# Power.net
KiCad netlist of a schematic drawn in Altium Designer
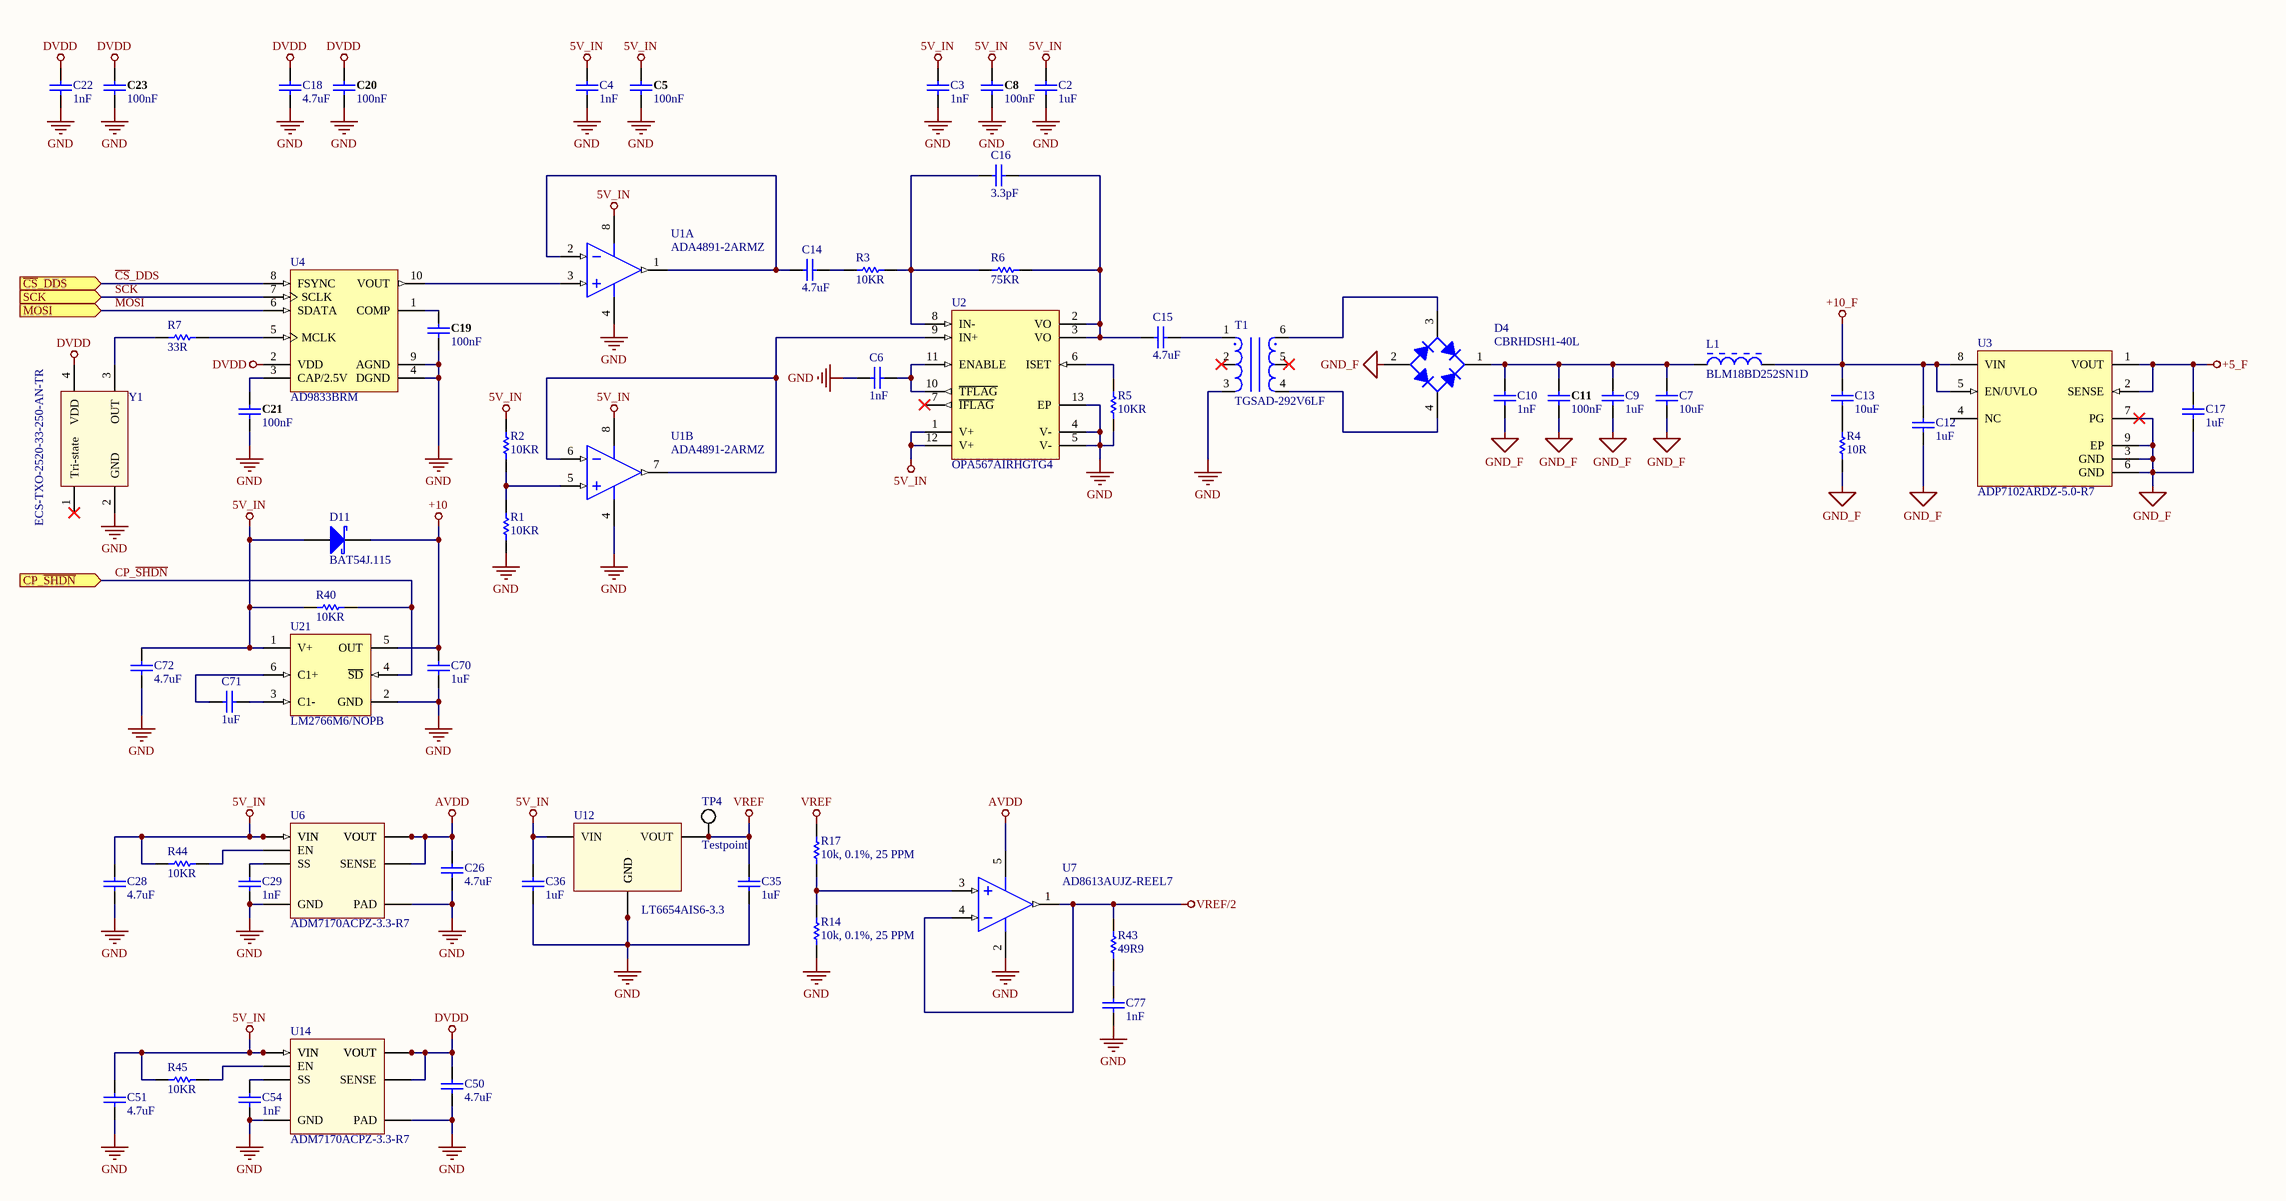
[diagram p0: Power.SchDoc]

(export (version "E")
  (design (tool "Eeschema 10.0.6"))
  (components
    (comp (ref "C2")
      (value "1uF")
      (footprint "CAPC1608X90X40LL15T20")
      (description "CC0603KRX5R7BB105")
      (fields (field (name "TOLERANCE") "±10%") (field (name "MANUFACTURER") "Yageo"))
      (libsource (lib "Altium Content Vault") (part "CAP-NP-2"))
    )
    (comp (ref "C3")
      (value "1nF")
      (footprint "CAPC1005X55X25ML5T10")
      (description "CC0402JRX7R9BB102")
      (fields (field (name "MANUFACTURER") "Yageo") (field (name "TOLERANCE") "10%"))
      (libsource (lib "Altium Content Vault") (part "CAP-NP-2"))
    )
    (comp (ref "C4")
      (value "1nF")
      (footprint "CAPC1005X55X25ML5T10")
      (description "CC0402JRX7R9BB102")
      (fields (field (name "MANUFACTURER") "Yageo") (field (name "TOLERANCE") "10%"))
      (libsource (lib "Altium Content Vault") (part "CAP-NP-2"))
    )
    (comp (ref "C5")
      (value "100nF")
      (footprint "CAPC1005")
      (description "CC0402KRX7R7BB104")
      (fields (field (name "TOLERANCE") "10 %") (field (name "PUBLISHER") "Altium"))
      (libsource (lib "Altium Content Vault") (part "CAP-NP"))
    )
    (comp (ref "C6")
      (value "1nF")
      (footprint "CAPC1005X55X25ML5T10")
      (description "CC0402JRX7R9BB102")
      (fields (field (name "MANUFACTURER") "Yageo") (field (name "TOLERANCE") "10%"))
      (libsource (lib "Altium Content Vault") (part "CAP-NP-2"))
    )
    (comp (ref "C7")
      (value "10uF")
      (footprint "CAPC2013X95X45ML10T25")
      (description "GRM219R61E106KA12D")
      (fields (field (name "MANUFACTURER") "Murata"))
      (libsource (lib "Altium Content Vault") (part "CAP"))
    )
    (comp (ref "C8")
      (value "100nF")
      (footprint "CAPC1005")
      (description "CC0402KRX7R7BB104")
      (fields (field (name "TOLERANCE") "10 %") (field (name "PUBLISHER") "Altium"))
      (libsource (lib "Altium Content Vault") (part "CAP-NP"))
    )
    (comp (ref "C9")
      (value "1uF")
      (footprint "CAPC1608X90X40LL15T20")
      (description "CC0603KRX5R7BB105")
      (fields (field (name "TOLERANCE") "±10%") (field (name "MANUFACTURER") "Yageo"))
      (libsource (lib "Altium Content Vault") (part "CAP-NP-2"))
    )
    (comp (ref "C10")
      (value "1nF")
      (footprint "CAPC1005X55X25ML5T10")
      (description "CC0402JRX7R9BB102")
      (fields (field (name "MANUFACTURER") "Yageo") (field (name "TOLERANCE") "10%"))
      (libsource (lib "Altium Content Vault") (part "CAP-NP-2"))
    )
    (comp (ref "C11")
      (value "100nF")
      (footprint "CAPC1005")
      (description "CC0402KRX7R7BB104")
      (fields (field (name "TOLERANCE") "10 %") (field (name "PUBLISHER") "Altium"))
      (libsource (lib "Altium Content Vault") (part "CAP-NP"))
    )
    (comp (ref "C12")
      (value "1uF")
      (footprint "CAPC1608X90X40LL15T20")
      (description "CC0603KRX5R7BB105")
      (fields (field (name "TOLERANCE") "±10%") (field (name "MANUFACTURER") "Yageo"))
      (libsource (lib "Altium Content Vault") (part "CAP-NP-2"))
    )
    (comp (ref "C13")
      (value "10uF")
      (footprint "CAPC2013X95X45ML10T25")
      (description "GRM219R61E106KA12D")
      (fields (field (name "MANUFACTURER") "Murata"))
      (libsource (lib "Altium Content Vault") (part "CAP"))
    )
    (comp (ref "C14")
      (value "4.7uF")
      (footprint "CAPC1608X90X40LL15T20")
      (description "CC0603KRX5R6BB475")
      (fields (field (name "TOLERANCE") "±10%") (field (name "MANUFACTURER") "Yageo"))
      (libsource (lib "Altium Content Vault") (part "CAP-NP-2"))
    )
    (comp (ref "C15")
      (value "4.7uF")
      (footprint "CAPC1608X90X40LL15T20")
      (description "CC0603KRX5R6BB475")
      (fields (field (name "TOLERANCE") "±10%") (field (name "MANUFACTURER") "Yageo"))
      (libsource (lib "Altium Content Vault") (part "CAP-NP-2"))
    )
    (comp (ref "C16")
      (value "3.3pF")
      (footprint "CAPC1005X55X25ML05T05")
      (description "CC0402CRNPO9BN3R3")
      (fields (field (name "TOLERANCE") "5%") (field (name "MANUFACTURER") "Yageo"))
      (libsource (lib "Altium Content Vault") (part "CAP-NP-2"))
    )
    (comp (ref "C17")
      (value "1uF")
      (footprint "CAPC1608X90X40LL15T20")
      (description "CC0603KRX5R7BB105")
      (fields (field (name "TOLERANCE") "±10%") (field (name "MANUFACTURER") "Yageo"))
      (libsource (lib "Altium Content Vault") (part "CAP-NP-2"))
    )
    (comp (ref "C18")
      (value "4.7uF")
      (footprint "CAPC1608X90X40LL15T20")
      (description "CC0603KRX5R6BB475")
      (fields (field (name "TOLERANCE") "±10%") (field (name "MANUFACTURER") "Yageo"))
      (libsource (lib "Altium Content Vault") (part "CAP-NP-2"))
    )
    (comp (ref "C19")
      (value "100nF")
      (footprint "CAPC1005")
      (description "CC0402KRX7R7BB104")
      (fields (field (name "TOLERANCE") "10 %") (field (name "PUBLISHER") "Altium"))
      (libsource (lib "Altium Content Vault") (part "CAP-NP"))
    )
    (comp (ref "C20")
      (value "100nF")
      (footprint "CAPC1005")
      (description "CC0402KRX7R7BB104")
      (fields (field (name "TOLERANCE") "10 %") (field (name "PUBLISHER") "Altium"))
      (libsource (lib "Altium Content Vault") (part "CAP-NP"))
    )
    (comp (ref "C21")
      (value "100nF")
      (footprint "CAPC1005")
      (description "CC0402KRX7R7BB104")
      (fields (field (name "TOLERANCE") "10 %") (field (name "PUBLISHER") "Altium"))
      (libsource (lib "Altium Content Vault") (part "CAP-NP"))
    )
    (comp (ref "C22")
      (value "1nF")
      (footprint "CAPC1005X55X25ML5T10")
      (description "CC0402JRX7R9BB102")
      (fields (field (name "MANUFACTURER") "Yageo") (field (name "TOLERANCE") "10%"))
      (libsource (lib "Altium Content Vault") (part "CAP-NP-2"))
    )
    (comp (ref "C23")
      (value "100nF")
      (footprint "CAPC1005")
      (description "CC0402KRX7R7BB104")
      (fields (field (name "TOLERANCE") "10 %") (field (name "PUBLISHER") "Altium"))
      (libsource (lib "Altium Content Vault") (part "CAP-NP"))
    )
    (comp (ref "C26")
      (value "4.7uF")
      (footprint "CAPC1608X90X40LL15T20")
      (description "CC0603KRX5R6BB475")
      (fields (field (name "TOLERANCE") "±10%") (field (name "MANUFACTURER") "Yageo"))
      (libsource (lib "Altium Content Vault") (part "CAP-NP-2"))
    )
    (comp (ref "C28")
      (value "4.7uF")
      (footprint "CAPC1608X90X40LL15T20")
      (description "CC0603KRX5R6BB475")
      (fields (field (name "TOLERANCE") "±10%") (field (name "MANUFACTURER") "Yageo"))
      (libsource (lib "Altium Content Vault") (part "CAP-NP-2"))
    )
    (comp (ref "C29")
      (value "1nF")
      (footprint "CAPC1005X55X25ML5T10")
      (description "CC0402JRX7R9BB102")
      (fields (field (name "MANUFACTURER") "Yageo") (field (name "TOLERANCE") "10%"))
      (libsource (lib "Altium Content Vault") (part "CAP-NP-2"))
    )
    (comp (ref "C35")
      (value "1uF")
      (footprint "CAPC1608X90X40LL15T20")
      (description "CC0603KRX5R7BB105")
      (fields (field (name "TOLERANCE") "±10%") (field (name "MANUFACTURER") "Yageo"))
      (libsource (lib "Altium Content Vault") (part "CAP-NP-2"))
    )
    (comp (ref "C36")
      (value "1uF")
      (footprint "CAPC1608X90X40LL15T20")
      (description "CC0603KRX5R7BB105")
      (fields (field (name "TOLERANCE") "±10%") (field (name "MANUFACTURER") "Yageo"))
      (libsource (lib "Altium Content Vault") (part "CAP-NP-2"))
    )
    (comp (ref "C50")
      (value "4.7uF")
      (footprint "CAPC1608X90X40LL15T20")
      (description "CC0603KRX5R6BB475")
      (fields (field (name "TOLERANCE") "±10%") (field (name "MANUFACTURER") "Yageo"))
      (libsource (lib "Altium Content Vault") (part "CAP-NP-2"))
    )
    (comp (ref "C51")
      (value "4.7uF")
      (footprint "CAPC1608X90X40LL15T20")
      (description "CC0603KRX5R6BB475")
      (fields (field (name "TOLERANCE") "±10%") (field (name "MANUFACTURER") "Yageo"))
      (libsource (lib "Altium Content Vault") (part "CAP-NP-2"))
    )
    (comp (ref "C54")
      (value "1nF")
      (footprint "CAPC1005X55X25ML5T10")
      (description "CC0402JRX7R9BB102")
      (fields (field (name "MANUFACTURER") "Yageo") (field (name "TOLERANCE") "10%"))
      (libsource (lib "Altium Content Vault") (part "CAP-NP-2"))
    )
    (comp (ref "C70")
      (value "1uF")
      (footprint "CAPC1608X90X40LL15T20")
      (description "CC0603KRX5R7BB105")
      (fields (field (name "TOLERANCE") "±10%") (field (name "MANUFACTURER") "Yageo"))
      (libsource (lib "Altium Content Vault") (part "CAP-NP-2"))
    )
    (comp (ref "C71")
      (value "1uF")
      (footprint "CAPC1608X90X40LL15T20")
      (description "CC0603KRX5R7BB105")
      (fields (field (name "TOLERANCE") "±10%") (field (name "MANUFACTURER") "Yageo"))
      (libsource (lib "Altium Content Vault") (part "CAP-NP-2"))
    )
    (comp (ref "C72")
      (value "4.7uF")
      (footprint "CAPC1608X90X40LL15T20")
      (description "CC0603KRX5R6BB475")
      (fields (field (name "TOLERANCE") "±10%") (field (name "MANUFACTURER") "Yageo"))
      (libsource (lib "Altium Content Vault") (part "CAP-NP-2"))
    )
    (comp (ref "C77")
      (value "1nF")
      (footprint "CAPC1005X55X25ML5T10")
      (description "CC0402JRX7R9BB102")
      (fields (field (name "MANUFACTURER") "Yageo") (field (name "TOLERANCE") "10%"))
      (libsource (lib "Altium Content Vault") (part "CAP-NP-2"))
    )
    (comp (ref "D4")
      (value "CBRHDSH1-40L")
      (footprint "HDDIP")
      (libsource (lib "LocalLib") (part "CBRHDSH1-40L"))
    )
    (comp (ref "D11")
      (value "BAT54J.115")
      (footprint "SOD-323")
      (libsource (lib "LocalLib") (part "BAT54J.115"))
    )
    (comp (ref "L1")
      (value "BLM18BD252SN1D")
      (footprint "MURA-BLM18-F-H1-CHIP-2_V")
      (fields (field (name "MANUFACTURER") "Murata"))
      (libsource (lib "Altium Content Vault") (part "MURA-FB-2"))
    )
    (comp (ref "R1")
      (value "10KR")
      (footprint "RESC1005X40X25LL05T10")
      (description "RC0402FR-0710KL")
      (fields (field (name "MANUFACTURER") "Yageo / Phycomp"))
      (libsource (lib "Altium Content Vault") (part "RES"))
    )
    (comp (ref "R2")
      (value "10KR")
      (footprint "RESC1005X40X25LL05T10")
      (description "RC0402FR-0710KL")
      (fields (field (name "MANUFACTURER") "Yageo / Phycomp"))
      (libsource (lib "Altium Content Vault") (part "RES"))
    )
    (comp (ref "R3")
      (value "10KR")
      (footprint "RESC1005X40X25LL05T10")
      (description "RC0402FR-0710KL")
      (fields (field (name "MANUFACTURER") "Yageo / Phycomp"))
      (libsource (lib "Altium Content Vault") (part "RES"))
    )
    (comp (ref "R4")
      (value "10R")
      (footprint "RESC1608X55X25LL10T15")
      (description "RC0603FR-0710RL")
      (fields (field (name "MANUFACTURER") "Yageo"))
      (libsource (lib "Altium Content Vault") (part "RES-2"))
    )
    (comp (ref "R5")
      (value "10KR")
      (footprint "RESC1005X40X25LL05T10")
      (description "RC0402FR-0710KL")
      (fields (field (name "MANUFACTURER") "Yageo / Phycomp"))
      (libsource (lib "Altium Content Vault") (part "RES"))
    )
    (comp (ref "R6")
      (value "75KR")
      (footprint "RESC1005X40X25LL05T10")
      (description "RC0402FR-0775KL")
      (fields (field (name "MANUFACTURER") "Yageo / Phycomp"))
      (libsource (lib "Altium Content Vault") (part "RES"))
    )
    (comp (ref "R7")
      (value "33R")
      (footprint "RESC1005X40X25LL05T10")
      (description "RC0402FR-0733RL")
      (fields (field (name "MANUFACTURER") "Yageo / Phycomp"))
      (libsource (lib "Altium Content Vault") (part "RES"))
    )
    (comp (ref "R14")
      (value "10k, 0.1%, 25 PPM")
      (footprint "RT0603")
      (description "RT0603BRD0710KL")
      (libsource (lib "LocalLib") (part "RT0603BRD0710KL"))
    )
    (comp (ref "R17")
      (value "10k, 0.1%, 25 PPM")
      (footprint "RT0603")
      (description "RT0603BRD0710KL")
      (libsource (lib "LocalLib") (part "RT0603BRD0710KL"))
    )
    (comp (ref "R40")
      (value "10KR")
      (footprint "RESC1005X40X25LL05T10")
      (description "RC0402FR-0710KL")
      (fields (field (name "MANUFACTURER") "Yageo / Phycomp"))
      (libsource (lib "Altium Content Vault") (part "RES"))
    )
    (comp (ref "R43")
      (value "49R9")
      (footprint "RESC1005X40X25LL05T10")
      (description "RC0402FR-0749R9L")
      (fields (field (name "MANUFACTURER") "Yageo / Phycomp"))
      (libsource (lib "Altium Content Vault") (part "RES"))
    )
    (comp (ref "R44")
      (value "10KR")
      (footprint "RESC1005X40X25LL05T10")
      (description "RC0402FR-0710KL")
      (fields (field (name "MANUFACTURER") "Yageo / Phycomp"))
      (libsource (lib "Altium Content Vault") (part "RES"))
    )
    (comp (ref "R45")
      (value "10KR")
      (footprint "RESC1005X40X25LL05T10")
      (description "RC0402FR-0710KL")
      (fields (field (name "MANUFACTURER") "Yageo / Phycomp"))
      (libsource (lib "Altium Content Vault") (part "RES"))
    )
    (comp (ref "T1")
      (value "TGSAD-292V6LF")
      (footprint "TGSAD-V6LF")
      (description "1:5")
      (libsource (lib "LocalLib") (part "TGSAD-292V6LF"))
    )
    (comp (ref "TP4")
      (value "Testpoint")
      (footprint "TESTPOINT")
      (libsource (lib "LocalLib") (part "Testpoint"))
    )
    (comp (ref "U1")
      (value "ADA4891-2ARMZ")
      (footprint "ADI-RM-8_L")
      (fields (field (name "GENERIC PART NUMBER") "ADA4891-2") (field (name "MANUFACTURER") "Analog Devices"))
      (libsource (lib "Altium Content Vault") (part "ADI-AD8XXX_823_A48X1-X-8"))
    )
    (comp (ref "U2")
      (value "OPA567AIRHGTG4")
      (footprint "TI-RHG12-3120X3120TP_V")
      (libsource (lib "Altium Content Vault") (part "TI-OPA567-RHG12"))
    )
    (comp (ref "U3")
      (value "ADP7102ARDZ-5.0-R7")
      (footprint "ADI-RD-8-2_N")
      (description "300 mA, Low Noise, CMOS LDO, 3.3 to 20 V Vin, 5 V Vout, Industrial, 8-pin SOIC (RD-8-2), Reel")
      (fields (field (name "MANUFACTURER") "Analog Devices"))
      (libsource (lib "Altium Content Vault") (part "ADI-ADP7102-RD-8-2"))
    )
    (comp (ref "U4")
      (value "AD9833BRM")
      (footprint "ADI-RM-10_N")
      (libsource (lib "Altium Content Vault") (part "ADI-AD9833-RM-10"))
    )
    (comp (ref "U6")
      (value "ADM7170ACPZ-3.3-R7")
      (footprint "LFCSP8")
      (libsource (lib "LocalLib") (part "ADM7170ACPZ-3.3-R7"))
    )
    (comp (ref "U7")
      (value "AD8613AUJZ-REEL7")
      (footprint "TSOT-23-5")
      (description "Low Cost Micropower, Low Noise CMOS\r\nRail-to-Rail, Input/Output Operational Amplifiers")
      (libsource (lib "LocalLib") (part "AD8613AUJZ-REEL7"))
    )
    (comp (ref "U12")
      (value "LT6654AIS6-3.3")
      (footprint "SOT-23-6")
      (description "Precision Wide Supply High Output Drive Low Noise Reference")
      (libsource (lib "LocalLib") (part "LT6654AIS6-3.3"))
    )
    (comp (ref "U14")
      (value "ADM7170ACPZ-3.3-R7")
      (footprint "LFCSP8")
      (libsource (lib "LocalLib") (part "ADM7170ACPZ-3.3-R7"))
    )
    (comp (ref "U21")
      (value "LM2766M6/NOPB")
      (footprint "DBV0006A_N")
      (description "Switched Capacitor Voltage Converter, 6-pin SOT-23, Pb-Free")
      (fields (field (name "MANUFACTURER") "Texas Instruments"))
      (libsource (lib "Altium Content Vault") (part "PM-CHP-LM2766M6-6"))
    )
    (comp (ref "Y1")
      (value "ECS-TXO-2520-33-250-AN-TR")
      (footprint "XTAL_ECS-TXO-2520-33-250")
      (libsource (lib "LocalLib") (part "ECS-TXO-2520-33-250-AN-TR"))
    )
  )
  (nets
    (net (code "1") (name "+5_F") (class "Default")
      (node (ref "C17") (pin "1") (pinfunction "1_1") (pintype "passive"))
      (node (ref "U3") (pin "1") (pinfunction "VOUT_1") (pintype "power_in"))
      (node (ref "U3") (pin "2") (pinfunction "SENSE_2") (pintype "input"))
    )
    (net (code "2") (name "+10") (class "Default")
      (node (ref "C70") (pin "2") (pinfunction "2_2") (pintype "passive"))
      (node (ref "D11") (pin "1") (pinfunction "K_1") (pintype "passive"))
      (node (ref "U21") (pin "5") (pinfunction "OUT_5") (pintype "power_in"))
    )
    (net (code "3") (name "+10_F") (class "Default")
      (node (ref "C12") (pin "1") (pinfunction "1_1") (pintype "passive"))
      (node (ref "C13") (pin "2") (pinfunction "2_2") (pintype "passive"))
      (node (ref "L1") (pin "2") (pinfunction "2_2") (pintype "passive"))
      (node (ref "U3") (pin "5") (pinfunction "EN/UVLO_5") (pintype "input"))
      (node (ref "U3") (pin "8") (pinfunction "VIN_8") (pintype "power_in"))
    )
    (net (code "4") (name "/CP_~{SHDN}") (class "Default")
      (node (ref "R40") (pin "1") (pinfunction "1_1") (pintype "passive"))
      (node (ref "U21") (pin "4") (pinfunction "~{SD}_4") (pintype "input"))
    )
    (net (code "5") (name "/MOSI") (class "Default")
      (node (ref "U4") (pin "6") (pinfunction "SDATA_6") (pintype "input"))
    )
    (net (code "6") (name "/SCK") (class "Default")
      (node (ref "U4") (pin "7") (pinfunction "SCLK_7") (pintype "input"))
    )
    (net (code "7") (name "/~{CS}_DDS") (class "Default")
      (node (ref "U4") (pin "8") (pinfunction "FSYNC_8") (pintype "input"))
    )
    (net (code "8") (name "5V_IN") (class "Default")
      (node (ref "C2") (pin "1") (pinfunction "1_1") (pintype "passive"))
      (node (ref "C28") (pin "2") (pinfunction "2_2") (pintype "passive"))
      (node (ref "C3") (pin "2") (pinfunction "2_2") (pintype "passive"))
      (node (ref "C36") (pin "1") (pinfunction "1_1") (pintype "passive"))
      (node (ref "C4") (pin "2") (pinfunction "2_2") (pintype "passive"))
      (node (ref "C5") (pin "1") (pinfunction "1_1") (pintype "passive"))
      (node (ref "C51") (pin "2") (pinfunction "2_2") (pintype "passive"))
      (node (ref "C72") (pin "2") (pinfunction "2_2") (pintype "passive"))
      (node (ref "C8") (pin "1") (pinfunction "1_1") (pintype "passive"))
      (node (ref "D11") (pin "2") (pinfunction "A_2") (pintype "passive"))
      (node (ref "R2") (pin "1") (pinfunction "1_1") (pintype "passive"))
      (node (ref "R40") (pin "2") (pinfunction "2_2") (pintype "passive"))
      (node (ref "R44") (pin "2") (pinfunction "2_2") (pintype "passive"))
      (node (ref "R45") (pin "2") (pinfunction "2_2") (pintype "passive"))
      (node (ref "U1") (pin "8") (pinfunction "+VS_8") (pintype "power_in"))
      (node (ref "U12") (pin "4") (pinfunction "VIN_4") (pintype "passive"))
      (node (ref "U14") (pin "7") (pinfunction "VIN_7") (pintype "input"))
      (node (ref "U14") (pin "8") (pinfunction "VIN_8") (pintype "input"))
      (node (ref "U2") (pin "1") (pinfunction "V+_1") (pintype "power_in"))
      (node (ref "U2") (pin "12") (pinfunction "V+_12") (pintype "power_in"))
      (node (ref "U21") (pin "1") (pinfunction "V+_1") (pintype "power_in"))
      (node (ref "U6") (pin "7") (pinfunction "VIN_7") (pintype "input"))
      (node (ref "U6") (pin "8") (pinfunction "VIN_8") (pintype "input"))
    )
    (net (code "9") (name "AVDD") (class "Default")
      (node (ref "C26") (pin "2") (pinfunction "2_2") (pintype "passive"))
      (node (ref "U6") (pin "1") (pinfunction "VOUT_1") (pintype "passive"))
      (node (ref "U6") (pin "2") (pinfunction "VOUT_2") (pintype "passive"))
      (node (ref "U6") (pin "3") (pinfunction "SENSE_3") (pintype "passive"))
      (node (ref "U7") (pin "5") (pinfunction "5_5") (pintype "passive"))
    )
    (net (code "10") (name "DVDD") (class "Default")
      (node (ref "C18") (pin "2") (pinfunction "2_2") (pintype "passive"))
      (node (ref "C20") (pin "1") (pinfunction "1_1") (pintype "passive"))
      (node (ref "C22") (pin "2") (pinfunction "2_2") (pintype "passive"))
      (node (ref "C23") (pin "1") (pinfunction "1_1") (pintype "passive"))
      (node (ref "C50") (pin "2") (pinfunction "2_2") (pintype "passive"))
      (node (ref "U14") (pin "1") (pinfunction "VOUT_1") (pintype "passive"))
      (node (ref "U14") (pin "2") (pinfunction "VOUT_2") (pintype "passive"))
      (node (ref "U14") (pin "3") (pinfunction "SENSE_3") (pintype "passive"))
      (node (ref "U4") (pin "2") (pinfunction "VDD_2") (pintype "power_in"))
      (node (ref "Y1") (pin "4") (pinfunction "VDD_4") (pintype "passive"))
    )
    (net (code "11") (name "GND") (class "Default")
      (node (ref "C18") (pin "1") (pinfunction "1_1") (pintype "passive"))
      (node (ref "C19") (pin "2") (pinfunction "2_2") (pintype "passive"))
      (node (ref "C2") (pin "2") (pinfunction "2_2") (pintype "passive"))
      (node (ref "C20") (pin "2") (pinfunction "2_2") (pintype "passive"))
      (node (ref "C21") (pin "2") (pinfunction "2_2") (pintype "passive"))
      (node (ref "C22") (pin "1") (pinfunction "1_1") (pintype "passive"))
      (node (ref "C23") (pin "2") (pinfunction "2_2") (pintype "passive"))
      (node (ref "C26") (pin "1") (pinfunction "1_1") (pintype "passive"))
      (node (ref "C28") (pin "1") (pinfunction "1_1") (pintype "passive"))
      (node (ref "C29") (pin "1") (pinfunction "1_1") (pintype "passive"))
      (node (ref "C3") (pin "1") (pinfunction "1_1") (pintype "passive"))
      (node (ref "C35") (pin "2") (pinfunction "2_2") (pintype "passive"))
      (node (ref "C36") (pin "2") (pinfunction "2_2") (pintype "passive"))
      (node (ref "C4") (pin "1") (pinfunction "1_1") (pintype "passive"))
      (node (ref "C5") (pin "2") (pinfunction "2_2") (pintype "passive"))
      (node (ref "C50") (pin "1") (pinfunction "1_1") (pintype "passive"))
      (node (ref "C51") (pin "1") (pinfunction "1_1") (pintype "passive"))
      (node (ref "C54") (pin "1") (pinfunction "1_1") (pintype "passive"))
      (node (ref "C6") (pin "2") (pinfunction "2_2") (pintype "passive"))
      (node (ref "C70") (pin "1") (pinfunction "1_1") (pintype "passive"))
      (node (ref "C72") (pin "1") (pinfunction "1_1") (pintype "passive"))
      (node (ref "C77") (pin "2") (pinfunction "2_2") (pintype "passive"))
      (node (ref "C8") (pin "2") (pinfunction "2_2") (pintype "passive"))
      (node (ref "R1") (pin "2") (pinfunction "2_2") (pintype "passive"))
      (node (ref "R14") (pin "1") (pinfunction "1_1") (pintype "passive"))
      (node (ref "R5") (pin "1") (pinfunction "1_1") (pintype "passive"))
      (node (ref "T1") (pin "3") (pinfunction "3_3") (pintype "passive"))
      (node (ref "U1") (pin "4") (pinfunction "-VS_4") (pintype "power_in"))
      (node (ref "U12") (pin "1") (pinfunction "GND_1") (pintype "passive"))
      (node (ref "U12") (pin "2") (pinfunction "GND_2") (pintype "passive"))
      (node (ref "U14") (pin "6") (pinfunction "GND_6") (pintype "passive"))
      (node (ref "U14") (pin "9") (pinfunction "PAD_9") (pintype "passive"))
      (node (ref "U2") (pin "13") (pinfunction "EP_13") (pintype "passive"))
      (node (ref "U2") (pin "4") (pinfunction "V-_4") (pintype "power_in"))
      (node (ref "U2") (pin "5") (pinfunction "V-_5") (pintype "power_in"))
      (node (ref "U21") (pin "2") (pinfunction "GND_2") (pintype "power_in"))
      (node (ref "U4") (pin "4") (pinfunction "DGND_4") (pintype "power_in"))
      (node (ref "U4") (pin "9") (pinfunction "AGND_9") (pintype "power_in"))
      (node (ref "U6") (pin "6") (pinfunction "GND_6") (pintype "passive"))
      (node (ref "U6") (pin "9") (pinfunction "PAD_9") (pintype "passive"))
      (node (ref "U7") (pin "2") (pinfunction "2_2") (pintype "passive"))
      (node (ref "Y1") (pin "2") (pinfunction "GND_2") (pintype "passive"))
    )
    (net (code "12") (name "GND_F") (class "Default")
      (node (ref "C10") (pin "1") (pinfunction "1_1") (pintype "passive"))
      (node (ref "C11") (pin "2") (pinfunction "2_2") (pintype "passive"))
      (node (ref "C12") (pin "2") (pinfunction "2_2") (pintype "passive"))
      (node (ref "C17") (pin "2") (pinfunction "2_2") (pintype "passive"))
      (node (ref "C7") (pin "1") (pinfunction "1_1") (pintype "passive"))
      (node (ref "C9") (pin "2") (pinfunction "2_2") (pintype "passive"))
      (node (ref "D4") (pin "2") (pinfunction "A_2") (pintype "passive"))
      (node (ref "R4") (pin "1") (pinfunction "1_1") (pintype "passive"))
      (node (ref "U3") (pin "3") (pinfunction "GND_3") (pintype "power_in"))
      (node (ref "U3") (pin "6") (pinfunction "GND_6") (pintype "power_in"))
      (node (ref "U3") (pin "7") (pinfunction "PG_7") (pintype "open_collector"))
      (node (ref "U3") (pin "9") (pinfunction "EP_9") (pintype "power_in"))
    )
    (net (code "13") (name "Net-(C13-Pad1)") (class "Default")
      (node (ref "C13") (pin "1") (pinfunction "1_1") (pintype "passive"))
      (node (ref "R4") (pin "2") (pinfunction "2_2") (pintype "passive"))
    )
    (net (code "14") (name "Net-(C14-Pad1)") (class "Default")
      (node (ref "C14") (pin "1") (pinfunction "1_1") (pintype "passive"))
      (node (ref "R3") (pin "1") (pinfunction "1_1") (pintype "passive"))
    )
    (net (code "15") (name "Net-(C15-Pad1)") (class "Default")
      (node (ref "C15") (pin "1") (pinfunction "1_1") (pintype "passive"))
      (node (ref "T1") (pin "1") (pinfunction "1_1") (pintype "passive"))
    )
    (net (code "16") (name "Net-(C15-Pad2)") (class "Default")
      (node (ref "C15") (pin "2") (pinfunction "2_2") (pintype "passive"))
      (node (ref "C16") (pin "2") (pinfunction "2_2") (pintype "passive"))
      (node (ref "R6") (pin "2") (pinfunction "2_2") (pintype "passive"))
      (node (ref "U2") (pin "2") (pinfunction "VO_2") (pintype "tri_state"))
      (node (ref "U2") (pin "3") (pinfunction "VO_3") (pintype "tri_state"))
    )
    (net (code "17") (name "Net-(C77-Pad1)") (class "Default")
      (node (ref "C77") (pin "1") (pinfunction "1_1") (pintype "passive"))
      (node (ref "R43") (pin "2") (pinfunction "2_2") (pintype "passive"))
    )
    (net (code "18") (name "Net-(D4-C-Pad3)") (class "Default")
      (node (ref "D4") (pin "3") (pinfunction "C_3") (pintype "passive"))
      (node (ref "T1") (pin "6") (pinfunction "6_6") (pintype "passive"))
    )
    (net (code "19") (name "Net-(D4-C-Pad4)") (class "Default")
      (node (ref "D4") (pin "4") (pinfunction "C_4") (pintype "passive"))
      (node (ref "T1") (pin "4") (pinfunction "4_4") (pintype "passive"))
    )
    (net (code "20") (name "Net-(D4-K)") (class "Default")
      (node (ref "C10") (pin "2") (pinfunction "2_2") (pintype "passive"))
      (node (ref "C11") (pin "1") (pinfunction "1_1") (pintype "passive"))
      (node (ref "C7") (pin "2") (pinfunction "2_2") (pintype "passive"))
      (node (ref "C9") (pin "1") (pinfunction "1_1") (pintype "passive"))
      (node (ref "D4") (pin "1") (pinfunction "K_1") (pintype "passive"))
      (node (ref "L1") (pin "1") (pinfunction "1_1") (pintype "passive"))
    )
    (net (code "21") (name "Net-(R14-Pad2)") (class "Default")
      (node (ref "R14") (pin "2") (pinfunction "2_2") (pintype "passive"))
      (node (ref "R17") (pin "1") (pinfunction "1_1") (pintype "passive"))
      (node (ref "U7") (pin "3") (pinfunction "3_3") (pintype "input"))
    )
    (net (code "22") (name "Net-(U1A-+IN_1)") (class "Default")
      (node (ref "U1") (pin "3") (pinfunction "+IN_1_3") (pintype "input"))
      (node (ref "U4") (pin "10") (pinfunction "VOUT_10") (pintype "output"))
    )
    (net (code "23") (name "Net-(U1A--IN_1)") (class "Default")
      (node (ref "C14") (pin "2") (pinfunction "2_2") (pintype "passive"))
      (node (ref "U1") (pin "1") (pinfunction "OUT_1_1") (pintype "output"))
      (node (ref "U1") (pin "2") (pinfunction "-IN_1_2") (pintype "input"))
    )
    (net (code "24") (name "Net-(U1B-+IN_2)") (class "Default")
      (node (ref "R1") (pin "1") (pinfunction "1_1") (pintype "passive"))
      (node (ref "R2") (pin "2") (pinfunction "2_2") (pintype "passive"))
      (node (ref "U1") (pin "5") (pinfunction "+IN_2_5") (pintype "input"))
    )
    (net (code "25") (name "Net-(U1B--IN_2)") (class "Default")
      (node (ref "U1") (pin "6") (pinfunction "-IN_2_6") (pintype "input"))
      (node (ref "U1") (pin "7") (pinfunction "OUT_2_7") (pintype "output"))
      (node (ref "U2") (pin "9") (pinfunction "IN+_9") (pintype "input"))
    )
    (net (code "26") (name "Net-(U2-ENABLE)") (class "Default")
      (node (ref "C6") (pin "1") (pinfunction "1_1") (pintype "passive"))
      (node (ref "U2") (pin "10") (pinfunction "~{TFLAG}_10") (pintype "output"))
      (node (ref "U2") (pin "11") (pinfunction "ENABLE_11") (pintype "input"))
    )
    (net (code "27") (name "Net-(U2-IN-)") (class "Default")
      (node (ref "C16") (pin "1") (pinfunction "1_1") (pintype "passive"))
      (node (ref "R3") (pin "2") (pinfunction "2_2") (pintype "passive"))
      (node (ref "R6") (pin "1") (pinfunction "1_1") (pintype "passive"))
      (node (ref "U2") (pin "8") (pinfunction "IN-_8") (pintype "input"))
    )
    (net (code "28") (name "Net-(U2-ISET)") (class "Default")
      (node (ref "R5") (pin "2") (pinfunction "2_2") (pintype "passive"))
      (node (ref "U2") (pin "6") (pinfunction "ISET_6") (pintype "input"))
    )
    (net (code "29") (name "Net-(U4-CAP{slash}2.5V)") (class "Default")
      (node (ref "C21") (pin "1") (pinfunction "1_1") (pintype "passive"))
      (node (ref "U4") (pin "3") (pinfunction "CAP/2.5V_3") (pintype "power_in"))
    )
    (net (code "30") (name "Net-(U4-COMP)") (class "Default")
      (node (ref "C19") (pin "1") (pinfunction "1_1") (pintype "passive"))
      (node (ref "U4") (pin "1") (pinfunction "COMP_1") (pintype "passive"))
    )
    (net (code "31") (name "Net-(U4-MCLK)") (class "Default")
      (node (ref "R7") (pin "2") (pinfunction "2_2") (pintype "passive"))
      (node (ref "U4") (pin "5") (pinfunction "MCLK_5") (pintype "input"))
    )
    (net (code "32") (name "Net-(U6-EN)") (class "Default")
      (node (ref "R44") (pin "1") (pinfunction "1_1") (pintype "passive"))
      (node (ref "U6") (pin "5") (pinfunction "EN_5") (pintype "passive"))
    )
    (net (code "33") (name "Net-(U6-SS)") (class "Default")
      (node (ref "C29") (pin "2") (pinfunction "2_2") (pintype "passive"))
      (node (ref "U6") (pin "4") (pinfunction "SS_4") (pintype "passive"))
    )
    (net (code "34") (name "Net-(U12-DNC-Pad3)") (class "Default")
      (node (ref "U12") (pin "3") (pinfunction "DNC_3") (pintype "passive"))
      (node (ref "U12") (pin "5") (pinfunction "DNC_5") (pintype "passive"))
    )
    (net (code "35") (name "Net-(U14-EN)") (class "Default")
      (node (ref "R45") (pin "1") (pinfunction "1_1") (pintype "passive"))
      (node (ref "U14") (pin "5") (pinfunction "EN_5") (pintype "passive"))
    )
    (net (code "36") (name "Net-(U14-SS)") (class "Default")
      (node (ref "C54") (pin "2") (pinfunction "2_2") (pintype "passive"))
      (node (ref "U14") (pin "4") (pinfunction "SS_4") (pintype "passive"))
    )
    (net (code "37") (name "Net-(U21-C1+)") (class "Default")
      (node (ref "C71") (pin "2") (pinfunction "2_2") (pintype "passive"))
      (node (ref "U21") (pin "6") (pinfunction "C1+_6") (pintype "input"))
    )
    (net (code "38") (name "Net-(U21-C1-)") (class "Default")
      (node (ref "C71") (pin "1") (pinfunction "1_1") (pintype "passive"))
      (node (ref "U21") (pin "3") (pinfunction "C1-_3") (pintype "input"))
    )
    (net (code "39") (name "Net-(Y1-OUT)") (class "Default")
      (node (ref "R7") (pin "1") (pinfunction "1_1") (pintype "passive"))
      (node (ref "Y1") (pin "3") (pinfunction "OUT_3") (pintype "passive"))
    )
    (net (code "40") (name "VREF") (class "Default")
      (node (ref "C35") (pin "1") (pinfunction "1_1") (pintype "passive"))
      (node (ref "R17") (pin "2") (pinfunction "2_2") (pintype "passive"))
      (node (ref "TP4") (pin "1") (pinfunction "1_1") (pintype "passive"))
      (node (ref "U12") (pin "6") (pinfunction "VOUT_6") (pintype "passive"))
    )
    (net (code "41") (name "VREF{slash}2") (class "Default")
      (node (ref "R43") (pin "1") (pinfunction "1_1") (pintype "passive"))
      (node (ref "U7") (pin "1") (pinfunction "1_1") (pintype "output"))
      (node (ref "U7") (pin "4") (pinfunction "4_4") (pintype "input"))
    )
    (net (code "42") (name "unconnected-(T1-Pad2)") (class "Default")
      (node (ref "T1") (pin "2") (pinfunction "2_2") (pintype "passive+no_connect"))
    )
    (net (code "43") (name "unconnected-(T1-Pad5)") (class "Default")
      (node (ref "T1") (pin "5") (pinfunction "5_5") (pintype "passive+no_connect"))
    )
    (net (code "44") (name "unconnected-(U2-~{IFLAG}-Pad7)") (class "Default")
      (node (ref "U2") (pin "7") (pinfunction "~{IFLAG}_7") (pintype "output+no_connect"))
    )
    (net (code "45") (name "unconnected-(U3-NC-Pad4)") (class "Default")
      (node (ref "U3") (pin "4") (pinfunction "NC_4") (pintype "passive"))
    )
    (net (code "46") (name "unconnected-(Y1-Tri-state-Pad1)") (class "Default")
      (node (ref "Y1") (pin "1") (pinfunction "Tri-state_1") (pintype "passive+no_connect"))
    )
  )
)
